# d-sub15.net
KiCad netlist of a schematic drawn in EasyEDA
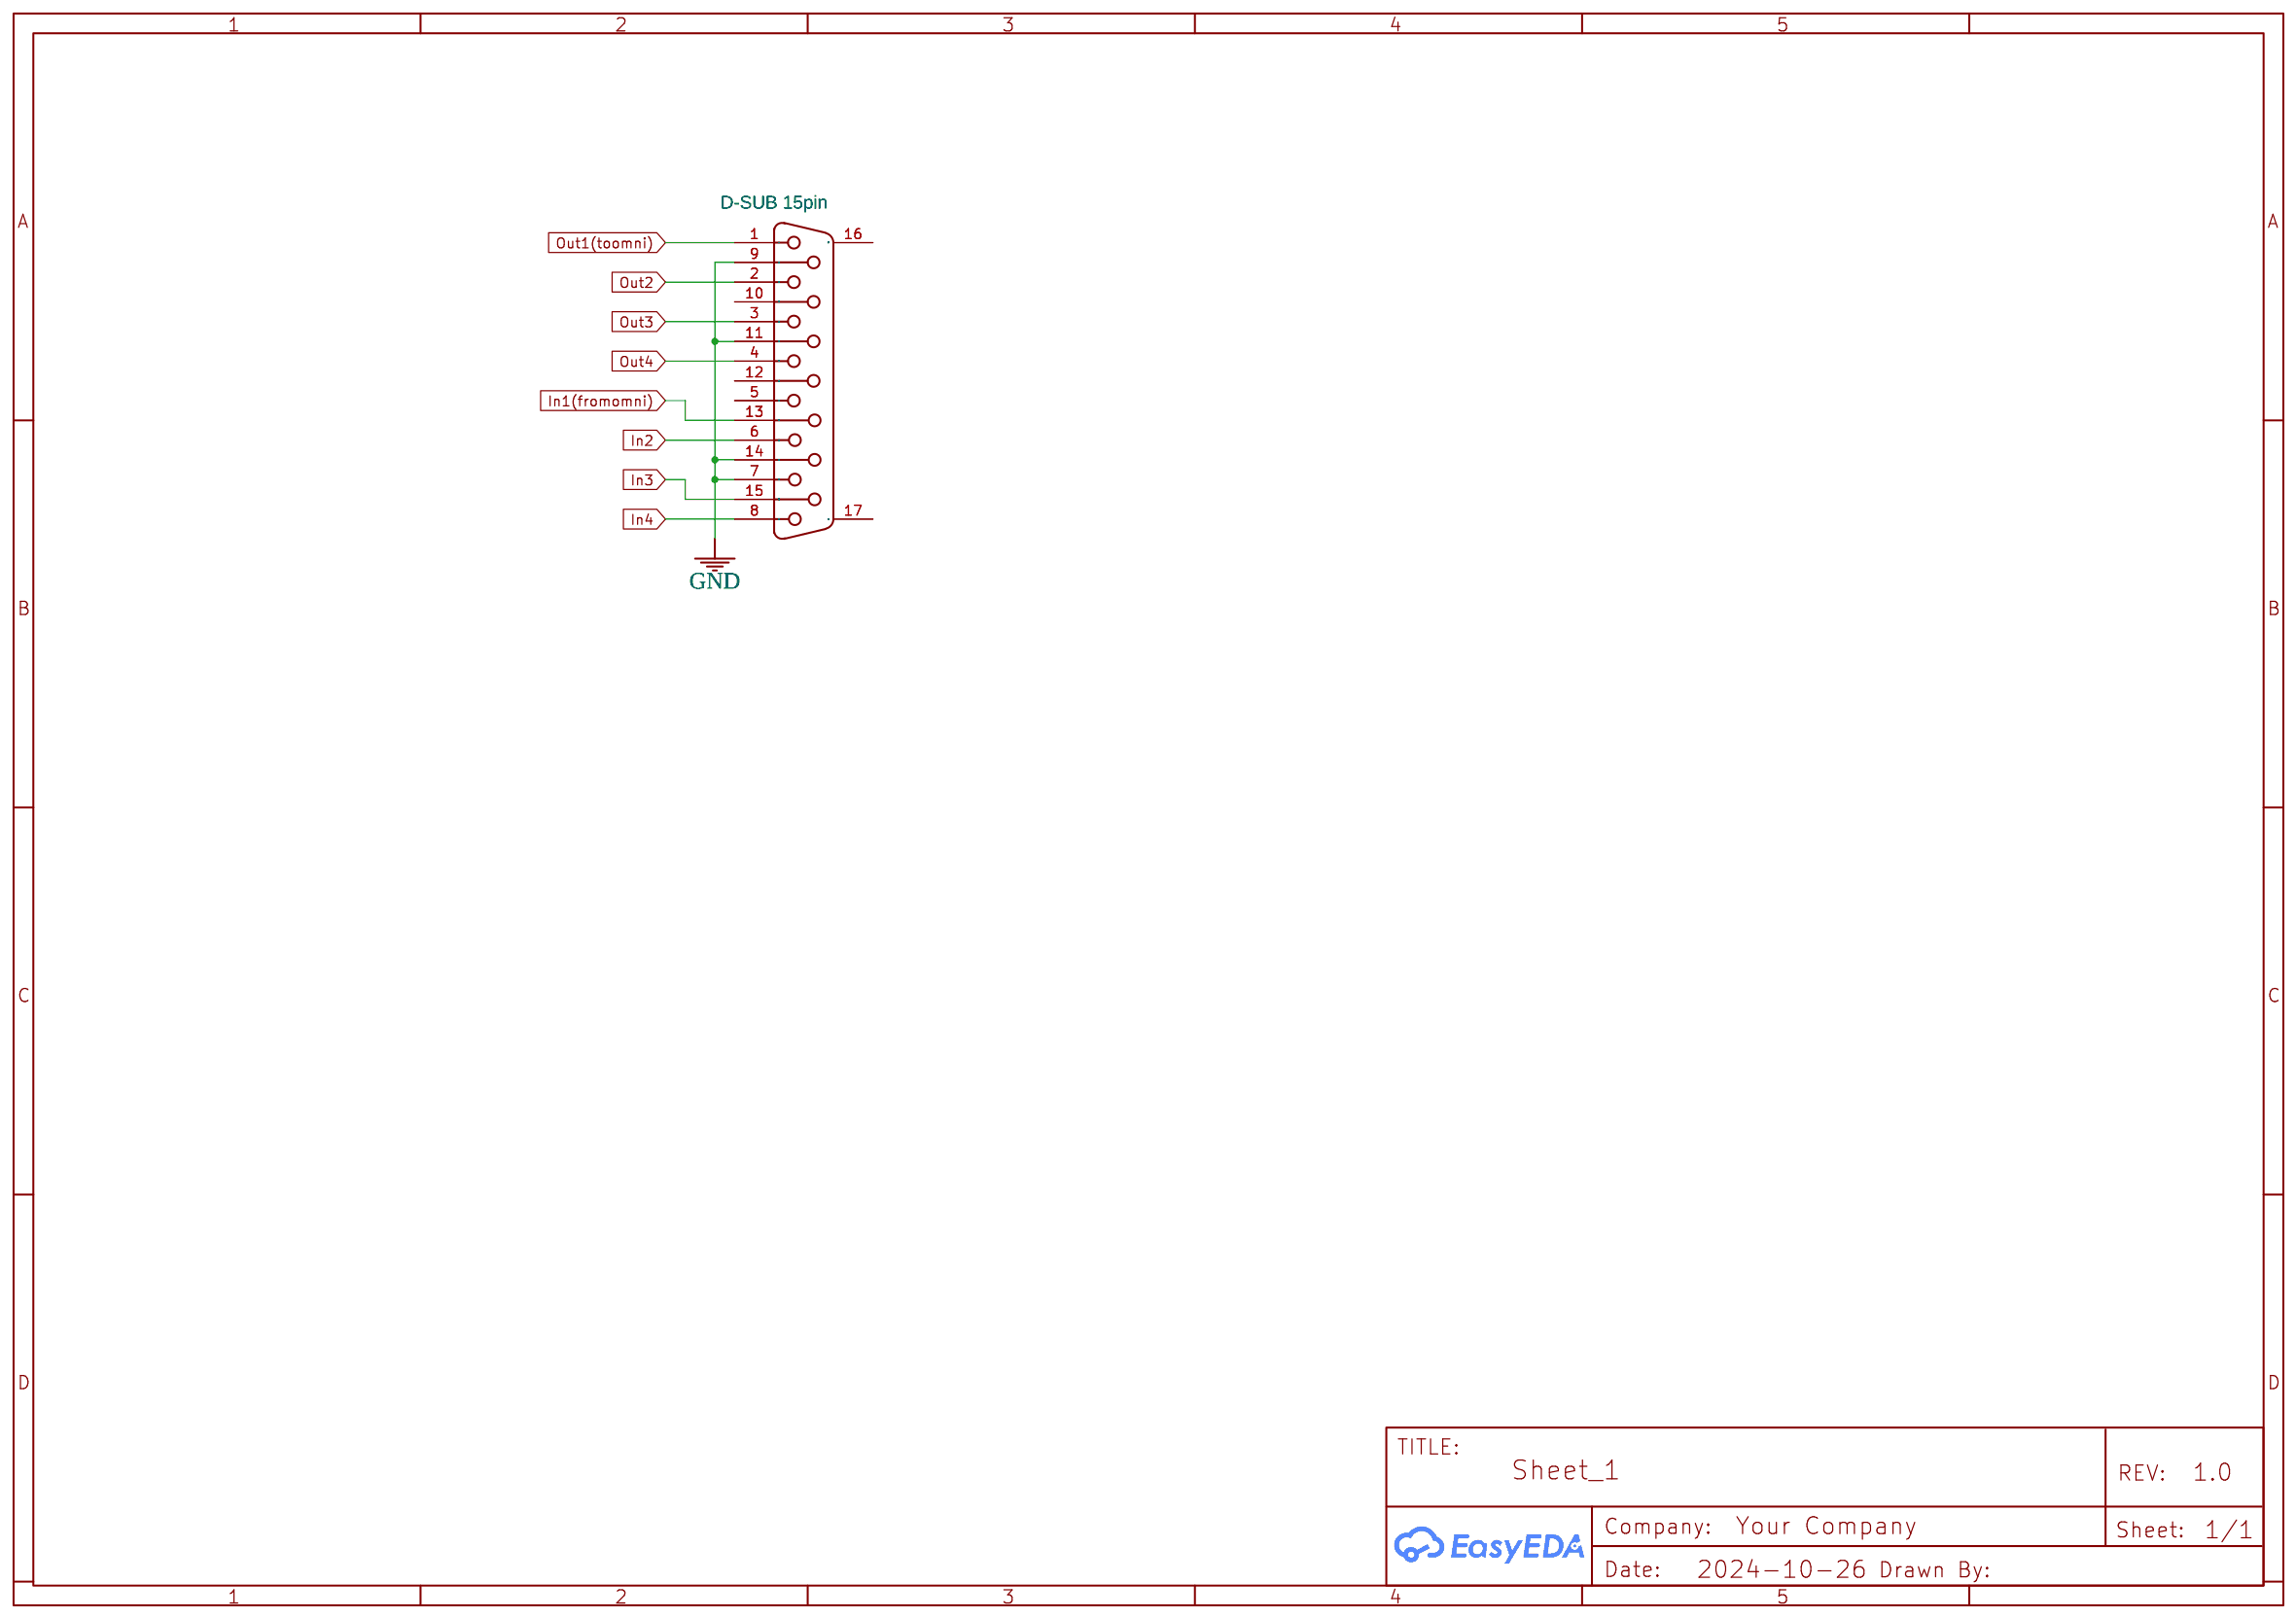
[diagram p0: schematic sheet]

(export (version "E")
  (design (tool "Eeschema 10.0.6"))
  (components
    (comp (ref "U1")
      (value "D-SUB 15pin")
      (fields
        (field (name "Manufacturer Part") "D-SUB-DP-15PYM-AW")
        (field (name "Manufacturer") "XUNPU(讯普)")
      )
      (libsource (lib "") (part "D-SUB-DP-15PYM-AW"))
    )
  )
  (nets
    (net (code "1") (name "GND") (class "Default")
      (node (ref "U1") (pin "11") (pinfunction "11_11") (pintype "input"))
      (node (ref "U1") (pin "14") (pinfunction "14_14") (pintype "input"))
      (node (ref "U1") (pin "7") (pinfunction "7_7") (pintype "input"))
      (node (ref "U1") (pin "9") (pinfunction "9_9") (pintype "input"))
    )
    (net (code "2") (name "In1(fromomni)") (class "Default")
      (node (ref "U1") (pin "13") (pinfunction "13_13") (pintype "input"))
    )
    (net (code "3") (name "In2") (class "Default")
      (node (ref "U1") (pin "6") (pinfunction "6_6") (pintype "input"))
    )
    (net (code "4") (name "In3") (class "Default")
      (node (ref "U1") (pin "15") (pinfunction "15_15") (pintype "input"))
    )
    (net (code "5") (name "In4") (class "Default")
      (node (ref "U1") (pin "8") (pinfunction "8_8") (pintype "input"))
    )
    (net (code "6") (name "Out1(toomni)") (class "Default")
      (node (ref "U1") (pin "1") (pinfunction "1_1") (pintype "input"))
    )
    (net (code "7") (name "Out2") (class "Default")
      (node (ref "U1") (pin "2") (pinfunction "2_2") (pintype "input"))
    )
    (net (code "8") (name "Out3") (class "Default")
      (node (ref "U1") (pin "3") (pinfunction "3_3") (pintype "input"))
    )
    (net (code "9") (name "Out4") (class "Default")
      (node (ref "U1") (pin "4") (pinfunction "4_4") (pintype "input"))
    )
    (net (code "10") (name "unconnected-(U1-MH1-Pad17)") (class "Default")
      (node (ref "U1") (pin "17") (pinfunction "MH1_17") (pintype "input"))
    )
    (net (code "11") (name "unconnected-(U1-MH2-Pad16)") (class "Default")
      (node (ref "U1") (pin "16") (pinfunction "MH2_16") (pintype "input"))
    )
    (net (code "12") (name "unconnected-(U1-Pad5)") (class "Default")
      (node (ref "U1") (pin "5") (pinfunction "5_5") (pintype "input"))
    )
    (net (code "13") (name "unconnected-(U1-Pad10)") (class "Default")
      (node (ref "U1") (pin "10") (pinfunction "10_10") (pintype "input"))
    )
    (net (code "14") (name "unconnected-(U1-Pad12)") (class "Default")
      (node (ref "U1") (pin "12") (pinfunction "12_12") (pintype "input"))
    )
  )
)
